# IV_PogopinConnector.net
KiCad netlist of a schematic drawn in Altium Designer
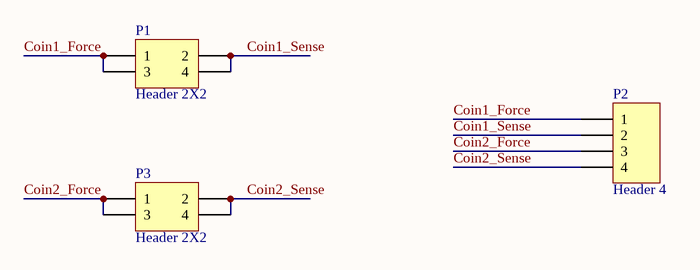
[diagram p0: IV_PogopinConnector.SchDoc]

(export (version "E")
  (design (tool "Eeschema 10.0.6"))
  (components
    (comp (ref "P1")
      (value "Header 2X2")
      (footprint "HDR2X2")
      (description "Header, 2-Pin, Dual row")
      (fields (field (name "PUBLISHER") "Altium Limited"))
      (libsource (lib "Miscellaneous Connectors") (part "Header 2X2"))
    )
    (comp (ref "P2")
      (value "Header 4")
      (footprint "HDR1X4")
      (description "Header, 4-Pin")
      (fields (field (name "PUBLISHER") "Altium Limited"))
      (libsource (lib "Miscellaneous Connectors") (part "Header 4"))
    )
    (comp (ref "P3")
      (value "Header 2X2")
      (footprint "HDR2X2")
      (description "Header, 2-Pin, Dual row")
      (fields (field (name "PUBLISHER") "Altium Limited"))
      (libsource (lib "Miscellaneous Connectors") (part "Header 2X2"))
    )
  )
  (nets
    (net (code "1") (name "/Coin1_Force") (class "Default")
      (node (ref "P1") (pin "1") (pinfunction "1_1") (pintype "passive"))
      (node (ref "P1") (pin "3") (pinfunction "3_3") (pintype "passive"))
      (node (ref "P2") (pin "1") (pinfunction "1_1") (pintype "passive"))
    )
    (net (code "2") (name "/Coin1_Sense") (class "Default")
      (node (ref "P1") (pin "2") (pinfunction "2_2") (pintype "passive"))
      (node (ref "P1") (pin "4") (pinfunction "4_4") (pintype "passive"))
      (node (ref "P2") (pin "2") (pinfunction "2_2") (pintype "passive"))
    )
    (net (code "3") (name "/Coin2_Force") (class "Default")
      (node (ref "P2") (pin "3") (pinfunction "3_3") (pintype "passive"))
      (node (ref "P3") (pin "1") (pinfunction "1_1") (pintype "passive"))
      (node (ref "P3") (pin "3") (pinfunction "3_3") (pintype "passive"))
    )
    (net (code "4") (name "/Coin2_Sense") (class "Default")
      (node (ref "P2") (pin "4") (pinfunction "4_4") (pintype "passive"))
      (node (ref "P3") (pin "2") (pinfunction "2_2") (pintype "passive"))
      (node (ref "P3") (pin "4") (pinfunction "4_4") (pintype "passive"))
    )
  )
)
